# main.net
KiCad netlist of a schematic drawn in Altium Designer
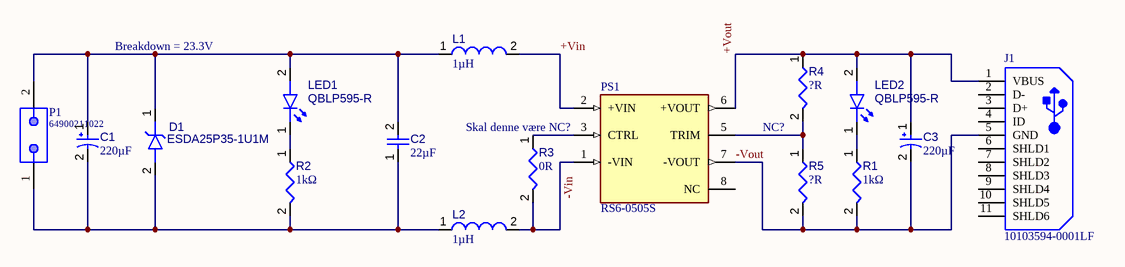
[diagram p0: main.SchDoc]

(export (version "E")
  (design (tool "Eeschema 10.0.6"))
  (components
    (comp (ref "C1")
      (value "220µF")
      (footprint "CAPPR65-500-1250X1000X1350")
      (description "Aluminum Electrolytic Capacitor, 220 uF, +/- 20%, 50 V, -40 to 85 degC, 2-Pin THD, RoHS, Bulk")
      (fields (field (name "TOLERANCE") "20%") (field (name "MANUFACTURER") "Panasonic"))
      (libsource (lib "Nordic Apps Workspace") (part "CAP-P-2"))
    )
    (comp (ref "C2")
      (value "22µF")
      (footprint "CAPC0805(2012)145_L")
      (description "Chip Capacitor, 22µF +/-40%, 16V, 0805, Thickness 1.45 mm")
      (fields (field (name "TOLERANCE") "5%") (field (name "Comment") "Capacitor 22µF +/-40% 16V 0805"))
      (libsource (lib "Nordic Apps Workspace") (part "CAP-NP-2"))
    )
    (comp (ref "C3")
      (value "220µF")
      (footprint "CAPPR65-500-1250X1000X1350")
      (description "Aluminum Electrolytic Capacitor, 220 uF, +/- 20%, 50 V, -40 to 85 degC, 2-Pin THD, RoHS, Bulk")
      (fields (field (name "TOLERANCE") "20%") (field (name "MANUFACTURER") "Panasonic"))
      (libsource (lib "Nordic Apps Workspace") (part "CAP-P-2"))
    )
    (comp (ref "D1")
      (value "ESDA25P35-1U1M")
      (footprint "STM-QFN1610")
      (description "TVS DIODE 22V 41V 1610")
      (libsource (lib "Nordic Apps Workspace") (part "D-TVS-AK-2"))
    )
    (comp (ref "J1")
      (value "10103594-0001LF")
      (footprint "FCI-10103594-0001LF_V")
      (description "Micro USB 2.0 B Receptacle, 5 Position, Height 3.24 mm, -55 to 85 degC, RoHS, Tape and Reel")
      (fields (field (name "MANUFACTURER") "FCI Electronics"))
      (libsource (lib "Nordic Apps Workspace") (part "USB-5-6SHLD"))
    )
    (comp (ref "L1")
      (value "1µH")
      (footprint "INDC2520X120X60ML20T20")
      (description "Chip Inductor, 1 uH, +/- 20%, 1 MHz, -55 to 125 degC, 1008 (2520 Metric), RoHS, Tape and Reel")
      (fields (field (name "TOLERANCE") "20%") (field (name "MANUFACTURER") "Murata"))
      (libsource (lib "Nordic Apps Workspace") (part "IND-2"))
    )
    (comp (ref "L2")
      (value "1µH")
      (footprint "INDC2520X120X60ML20T20")
      (description "Chip Inductor, 1 uH, +/- 20%, 1 MHz, -55 to 125 degC, 1008 (2520 Metric), RoHS, Tape and Reel")
      (fields (field (name "TOLERANCE") "20%") (field (name "MANUFACTURER") "Murata"))
      (libsource (lib "Nordic Apps Workspace") (part "IND-2"))
    )
    (comp (ref "LED1")
      (value "QBLP595-R")
      (footprint "QTB-QBLP595_V")
      (description "Chip LED 0402, Red, 0.02 A, 2.0 to 2.5 V, -40 to 80 degC, 2-Pin SMD, RoHS, Tape and Reel")
      (libsource (lib "Nordic Apps Workspace") (part "LED-KA-2"))
    )
    (comp (ref "LED2")
      (value "QBLP595-R")
      (footprint "QTB-QBLP595_V")
      (description "Chip LED 0402, Red, 0.02 A, 2.0 to 2.5 V, -40 to 80 degC, 2-Pin SMD, RoHS, Tape and Reel")
      (libsource (lib "Nordic Apps Workspace") (part "LED-KA-2"))
    )
    (comp (ref "P1")
      (value "64900211022")
      (footprint "Altium_WR-MPC3 (rev18b):66200221022")
      (description "THT Male Header WR-MPC3, with Snap-in Plastic Pegs, Right Angled, Dual Row, pitch 3 mm, 2 pins")
      (fields (field (name "PART NUMBER") "66200221022") (field (name "PUBLISHER") "Wurth Elektronik"))
      (libsource (lib "Altium_WR-MPC3 (rev18b)") (part "66200221022"))
    )
    (comp (ref "PS1")
      (value "RS6-0505S")
      (footprint "CONV_RS6-0505S")
      (description "6 Watt SIP8 Single and Dual Output")
      (libsource (lib "RS6-0505S") (part "RS6-0505S"))
    )
    (comp (ref "R1")
      (value "1kΩ")
      (footprint "RESC0805(2012)_L")
      (description "1K 0.125W 5% 0805 (2012 Metric)  SMD")
      (fields (field (name "POWER") "0.125W") (field (name "TOLERANCE") "5%"))
      (libsource (lib "Nordic Apps Workspace") (part "1KR5J"))
    )
    (comp (ref "R2")
      (value "1kΩ")
      (footprint "RESC0805(2012)_L")
      (description "1K 0.125W 5% 0805 (2012 Metric)  SMD")
      (fields (field (name "POWER") "0.125W") (field (name "TOLERANCE") "5%"))
      (libsource (lib "Nordic Apps Workspace") (part "1KR5J"))
    )
    (comp (ref "R3")
      (value "0R")
      (footprint "RESC0805(2012)_L")
      (description "0R 0805 (2012 Metric)  SMD")
      (fields (field (name "POWER") "0.125W") (field (name "TOLERANCE") "5%"))
      (libsource (lib "Nordic Apps Workspace") (part "1KR5J"))
    )
    (comp (ref "R4")
      (value "?R")
      (footprint "RESC0805(2012)_L")
      (description "0R 0805 (2012 Metric)  SMD")
      (fields (field (name "POWER") "0.125W") (field (name "TOLERANCE") "5%"))
      (libsource (lib "Nordic Apps Workspace") (part "1KR5J"))
    )
    (comp (ref "R5")
      (value "?R")
      (footprint "RESC0805(2012)_L")
      (description "0R 0805 (2012 Metric)  SMD")
      (fields (field (name "POWER") "0.125W") (field (name "TOLERANCE") "5%"))
      (libsource (lib "Nordic Apps Workspace") (part "1KR5J"))
    )
  )
  (nets
    (net (code "1") (name "/+Vin") (class "Default")
      (node (ref "L1") (pin "2") (pinfunction "2_2") (pintype "passive"))
      (node (ref "PS1") (pin "2") (pinfunction "+VIN_2") (pintype "input"))
    )
    (net (code "2") (name "/+Vout") (class "Default")
      (node (ref "C3") (pin "1") (pinfunction "1_1") (pintype "passive"))
      (node (ref "J1") (pin "1") (pinfunction "VBUS_1") (pintype "passive"))
      (node (ref "LED2") (pin "2") (pinfunction "A_2") (pintype "passive"))
      (node (ref "PS1") (pin "6") (pinfunction "+VOUT_6") (pintype "output"))
      (node (ref "R4") (pin "1") (pinfunction "1_1") (pintype "passive"))
    )
    (net (code "3") (name "/-Vin") (class "Default")
      (node (ref "L2") (pin "2") (pinfunction "2_2") (pintype "passive"))
      (node (ref "PS1") (pin "1") (pinfunction "-VIN_1") (pintype "input"))
      (node (ref "R3") (pin "2") (pinfunction "2_2") (pintype "passive"))
    )
    (net (code "4") (name "/-Vout") (class "Default")
      (node (ref "C3") (pin "2") (pinfunction "2_2") (pintype "passive"))
      (node (ref "J1") (pin "5") (pinfunction "GND_5") (pintype "passive"))
      (node (ref "PS1") (pin "7") (pinfunction "-VOUT_7") (pintype "output"))
      (node (ref "R1") (pin "2") (pinfunction "2_2") (pintype "passive"))
      (node (ref "R5") (pin "2") (pinfunction "2_2") (pintype "passive"))
    )
    (net (code "5") (name "Net-(C1-Pad2)") (class "Default")
      (node (ref "C1") (pin "2") (pinfunction "2_2") (pintype "passive"))
      (node (ref "C2") (pin "1") (pinfunction "1_1") (pintype "passive"))
      (node (ref "D1") (pin "2") (pinfunction "A_2") (pintype "passive"))
      (node (ref "L2") (pin "1") (pinfunction "1_1") (pintype "passive"))
      (node (ref "P1") (pin "1") (pinfunction "1_1") (pintype "passive"))
      (node (ref "R2") (pin "2") (pinfunction "2_2") (pintype "passive"))
    )
    (net (code "6") (name "Net-(LED1-A)") (class "Default")
      (node (ref "C1") (pin "1") (pinfunction "1_1") (pintype "passive"))
      (node (ref "C2") (pin "2") (pinfunction "2_2") (pintype "passive"))
      (node (ref "D1") (pin "1") (pinfunction "A_1") (pintype "passive"))
      (node (ref "L1") (pin "1") (pinfunction "1_1") (pintype "passive"))
      (node (ref "LED1") (pin "2") (pinfunction "A_2") (pintype "passive"))
      (node (ref "P1") (pin "2") (pinfunction "2_2") (pintype "passive"))
    )
    (net (code "7") (name "Net-(LED1-K)") (class "Default")
      (node (ref "LED1") (pin "1") (pinfunction "K_1") (pintype "passive"))
      (node (ref "R2") (pin "1") (pinfunction "1_1") (pintype "passive"))
    )
    (net (code "8") (name "Net-(LED2-K)") (class "Default")
      (node (ref "LED2") (pin "1") (pinfunction "K_1") (pintype "passive"))
      (node (ref "R1") (pin "1") (pinfunction "1_1") (pintype "passive"))
    )
    (net (code "9") (name "Net-(PS1-CTRL)") (class "Default")
      (node (ref "PS1") (pin "3") (pinfunction "CTRL_3") (pintype "input"))
      (node (ref "R3") (pin "1") (pinfunction "1_1") (pintype "passive"))
    )
    (net (code "10") (name "Net-(PS1-TRIM)") (class "Default")
      (node (ref "PS1") (pin "5") (pinfunction "TRIM_5") (pintype "passive"))
      (node (ref "R4") (pin "2") (pinfunction "2_2") (pintype "passive"))
      (node (ref "R5") (pin "1") (pinfunction "1_1") (pintype "passive"))
    )
    (net (code "11") (name "unconnected-(J1-D+-Pad3)") (class "Default")
      (node (ref "J1") (pin "3") (pinfunction "D+_3") (pintype "passive"))
    )
    (net (code "12") (name "unconnected-(J1-D--Pad2)") (class "Default")
      (node (ref "J1") (pin "2") (pinfunction "D-_2") (pintype "passive"))
    )
    (net (code "13") (name "unconnected-(J1-ID-Pad4)") (class "Default")
      (node (ref "J1") (pin "4") (pinfunction "ID_4") (pintype "passive"))
    )
    (net (code "14") (name "unconnected-(J1-SHLD1-Pad6)") (class "Default")
      (node (ref "J1") (pin "6") (pinfunction "SHLD1_6") (pintype "passive"))
    )
    (net (code "15") (name "unconnected-(J1-SHLD2-Pad7)") (class "Default")
      (node (ref "J1") (pin "7") (pinfunction "SHLD2_7") (pintype "passive"))
    )
    (net (code "16") (name "unconnected-(J1-SHLD3-Pad8)") (class "Default")
      (node (ref "J1") (pin "8") (pinfunction "SHLD3_8") (pintype "passive"))
    )
    (net (code "17") (name "unconnected-(J1-SHLD4-Pad9)") (class "Default")
      (node (ref "J1") (pin "9") (pinfunction "SHLD4_9") (pintype "passive"))
    )
    (net (code "18") (name "unconnected-(J1-SHLD5-Pad10)") (class "Default")
      (node (ref "J1") (pin "10") (pinfunction "SHLD5_10") (pintype "passive"))
    )
    (net (code "19") (name "unconnected-(J1-SHLD6-Pad11)") (class "Default")
      (node (ref "J1") (pin "11") (pinfunction "SHLD6_11") (pintype "passive"))
    )
    (net (code "20") (name "unconnected-(PS1-NC-Pad8)") (class "Default")
      (node (ref "PS1") (pin "8") (pinfunction "NC_8") (pintype "passive"))
    )
  )
)
